# HT-TRS-Interface-Schematic.net
KiCad netlist of a schematic drawn in Altium Designer
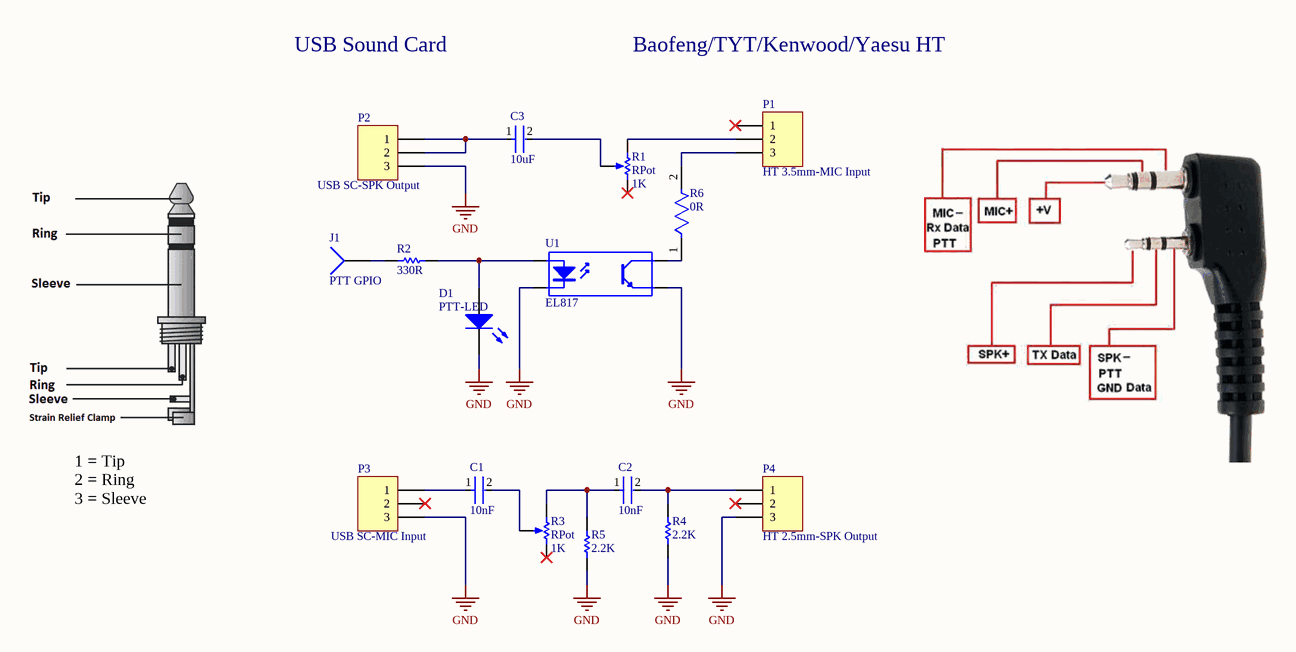
[diagram p0: HT-TRS-Interface-Schematic.SchDoc]

(export (version "E")
  (design (tool "Eeschema 10.0.6"))
  (components
    (comp (ref "C1")
      (value "10nF")
      (footprint "FP-CC0603-DA-MFG")
      (description "CAP CER 10000PF 25V X7R 0603")
      (fields (field (name "TOLERANCE") "0.1") (field (name "MANUFACTURER") "YAGEO"))
      (libsource (lib "Altium Content Vault") (part "11868f565c42a9108669ba33697ecf6"))
    )
    (comp (ref "C2")
      (value "10nF")
      (footprint "FP-CC0603-DA-MFG")
      (description "CAP CER 10000PF 25V X7R 0603")
      (fields (field (name "TOLERANCE") "0.1") (field (name "MANUFACTURER") "YAGEO"))
      (libsource (lib "Altium Content Vault") (part "11868f565c42a9108669ba33697ecf6"))
    )
    (comp (ref "C3")
      (value "10uF")
      (footprint "FP-C1608-MFG")
      (description "CAP CER 10UF 16V X5R 0603")
      (fields
        (field (name "OCTOPART") "https://octopart.com/c1608x5r1c106m080ab-tdk-26013480")
        (field (name "MANUFACTURER") "TDK Corporation")
      )
      (libsource (lib "Altium Content Vault") (part "11868f565c42a9108669ba33697ecf6"))
    )
    (comp (ref "D1")
      (value "PTT-LED")
      (footprint "3.2X1.6X1.1")
      (description "Typical RED, GREEN, YELLOW, AMBER GaAs LED")
      (fields (field (name "PUBLISHER") "Altium Limited"))
      (libsource (lib "Miscellaneous Devices") (part "LED2"))
    )
    (comp (ref "J1")
      (value "PTT GPIO")
      (footprint "PIN1")
      (description "Socket")
      (fields (field (name "PUBLISHER") "Altium Limited"))
      (libsource (lib "Miscellaneous Connectors") (part "Socket"))
    )
    (comp (ref "P1")
      (value "HT 3.5mm-MIC Input")
      (footprint "MHDR1X3")
      (description "Header, 3-Pin")
      (fields (field (name "PUBLISHER") "Altium Limited"))
      (libsource (lib "") (part "MHDR1X3_1"))
    )
    (comp (ref "P2")
      (value "USB SC-SPK Output")
      (footprint "MHDR1X3")
      (description "Header, 3-Pin")
      (fields (field (name "PUBLISHER") "Altium Limited"))
      (libsource (lib "Miscellaneous Connectors") (part "MHDR1X3"))
    )
    (comp (ref "P3")
      (value "USB SC-MIC Input")
      (footprint "MHDR1X3")
      (description "Header, 3-Pin")
      (fields (field (name "PUBLISHER") "Altium Limited"))
      (libsource (lib "Miscellaneous Connectors") (part "MHDR1X3"))
    )
    (comp (ref "P4")
      (value "HT 2.5mm-SPK Output")
      (footprint "MHDR1X3")
      (description "Header, 3-Pin")
      (fields (field (name "PUBLISHER") "Altium Limited"))
      (libsource (lib "") (part "MHDR1X3_1"))
    )
    (comp (ref "R1")
      (value "RPot")
      (footprint "VR5")
      (description "Potentiometer")
      (fields (field (name "ALTIUM_VALUE") "1K") (field (name "PUBLISHER") "Altium Limited"))
      (libsource (lib "Miscellaneous Devices") (part "RPot"))
    )
    (comp (ref "R2")
      (value "330R")
      (footprint "RESC1608X55X30LL15T15")
      (description "Chip Resistor, 330 Ohm, +/- 1%, 0.1 W, -55 to 155 degC, 0603 (1608 Metric), RoHS, Tape and Reel")
      (libsource (lib "Altium Content Vault") (part "RES-2"))
    )
    (comp (ref "R3")
      (value "RPot")
      (footprint "VR5")
      (description "Potentiometer")
      (fields (field (name "ALTIUM_VALUE") "1K") (field (name "PUBLISHER") "Altium Limited"))
      (libsource (lib "Miscellaneous Devices") (part "RPot"))
    )
    (comp (ref "R4")
      (value "2.2K")
      (footprint "RESC1608X55X30ML20T20")
      (fields (field (name "MANUFACTURER") "Panasonic") (field (name "PART NUMBER") "ERA3AEB222V"))
      (libsource (lib "Altium Content Vault") (part "RES"))
    )
    (comp (ref "R5")
      (value "2.2K")
      (footprint "RESC1608X55X30ML20T20")
      (fields (field (name "MANUFACTURER") "Panasonic") (field (name "PART NUMBER") "ERA3AEB222V"))
      (libsource (lib "Altium Content Vault") (part "RES"))
    )
    (comp (ref "R6")
      (value "0R")
      (footprint "FP-ERJ-3GEY0R00V-MFG")
      (description "RES SMD 0 OHM JUMPER 1/10W 0603")
      (fields (field (name "TOLERANCE") "5%") (field (name "MANUFACTURER PART NUMBER") "ERJ-3GEY0R00V"))
      (libsource (lib "Altium Content Vault") (part "1029c3af85768c4190bb7ad29bc67b5"))
    )
    (comp (ref "U1")
      (value "EL817")
      (footprint "DIP-4")
      (description "4-Pin Phototransistor Optocoupler")
      (fields (field (name "PUBLISHER") "Altium Limited"))
      (libsource (lib "Miscellaneous Devices") (part "Optoisolator1"))
    )
  )
  (nets
    (net (code "1") (name "GND") (class "Default")
      (node (ref "D1") (pin "2") (pinfunction "K_2") (pintype "passive"))
      (node (ref "P2") (pin "3") (pinfunction "3_3") (pintype "passive"))
      (node (ref "P3") (pin "3") (pinfunction "3_3") (pintype "passive"))
      (node (ref "P4") (pin "3") (pinfunction "3_3") (pintype "passive"))
      (node (ref "R4") (pin "1") (pinfunction "1_1") (pintype "passive"))
      (node (ref "R5") (pin "1") (pinfunction "1_1") (pintype "passive"))
      (node (ref "U1") (pin "2") (pinfunction "K_2") (pintype "passive"))
      (node (ref "U1") (pin "3") (pinfunction "E_3") (pintype "passive"))
    )
    (net (code "2") (name "Net-(C1-Pad1)") (class "Default")
      (node (ref "C1") (pin "1") (pinfunction "1_1") (pintype "passive"))
      (node (ref "P3") (pin "1") (pinfunction "1_1") (pintype "passive"))
    )
    (net (code "3") (name "Net-(C2-Pad2)") (class "Default")
      (node (ref "C2") (pin "2") (pinfunction "2_2") (pintype "passive"))
      (node (ref "P4") (pin "1") (pinfunction "1_1") (pintype "passive"))
      (node (ref "R4") (pin "2") (pinfunction "2_2") (pintype "passive"))
    )
    (net (code "4") (name "Net-(C3-Pad1)") (class "Default")
      (node (ref "C3") (pin "1") (pinfunction "1_1") (pintype "passive"))
      (node (ref "P2") (pin "1") (pinfunction "1_1") (pintype "passive"))
      (node (ref "P2") (pin "2") (pinfunction "2_2") (pintype "passive"))
    )
    (net (code "5") (name "Net-(D1-A)") (class "Default")
      (node (ref "D1") (pin "1") (pinfunction "A_1") (pintype "passive"))
      (node (ref "R2") (pin "2") (pinfunction "2_2") (pintype "passive"))
      (node (ref "U1") (pin "1") (pinfunction "A_1") (pintype "passive"))
    )
    (net (code "6") (name "Net-(J1-Pad1)") (class "Default")
      (node (ref "J1") (pin "1") (pinfunction "1_1") (pintype "passive"))
      (node (ref "R2") (pin "1") (pinfunction "1_1") (pintype "passive"))
    )
    (net (code "7") (name "Net-(P1-Pad3)") (class "Default")
      (node (ref "P1") (pin "3") (pinfunction "3_3") (pintype "passive"))
      (node (ref "R6") (pin "2") (pinfunction "2_2") (pintype "passive"))
    )
    (net (code "8") (name "Net-(R1-TAP)") (class "Default")
      (node (ref "C3") (pin "2") (pinfunction "2_2") (pintype "passive"))
      (node (ref "R1") (pin "3") (pinfunction "TAP_3") (pintype "passive"))
    )
    (net (code "9") (name "Net-(R1-TOP)") (class "Default")
      (node (ref "P1") (pin "2") (pinfunction "2_2") (pintype "passive"))
      (node (ref "R1") (pin "1") (pinfunction "TOP_1") (pintype "passive"))
    )
    (net (code "10") (name "Net-(R3-TAP)") (class "Default")
      (node (ref "C1") (pin "2") (pinfunction "2_2") (pintype "passive"))
      (node (ref "R3") (pin "3") (pinfunction "TAP_3") (pintype "passive"))
    )
    (net (code "11") (name "Net-(R3-TOP)") (class "Default")
      (node (ref "C2") (pin "1") (pinfunction "1_1") (pintype "passive"))
      (node (ref "R3") (pin "1") (pinfunction "TOP_1") (pintype "passive"))
      (node (ref "R5") (pin "2") (pinfunction "2_2") (pintype "passive"))
    )
    (net (code "12") (name "Net-(U1-C)") (class "Default")
      (node (ref "R6") (pin "1") (pinfunction "1_1") (pintype "passive"))
      (node (ref "U1") (pin "4") (pinfunction "C_4") (pintype "passive"))
    )
    (net (code "13") (name "unconnected-(P1-Pad1)") (class "Default")
      (node (ref "P1") (pin "1") (pinfunction "1_1") (pintype "passive+no_connect"))
    )
    (net (code "14") (name "unconnected-(P3-Pad2)") (class "Default")
      (node (ref "P3") (pin "2") (pinfunction "2_2") (pintype "passive+no_connect"))
    )
    (net (code "15") (name "unconnected-(P4-Pad2)") (class "Default")
      (node (ref "P4") (pin "2") (pinfunction "2_2") (pintype "passive+no_connect"))
    )
    (net (code "16") (name "unconnected-(R1-BOT-Pad2)") (class "Default")
      (node (ref "R1") (pin "2") (pinfunction "BOT_2") (pintype "passive+no_connect"))
    )
    (net (code "17") (name "unconnected-(R3-BOT-Pad2)") (class "Default")
      (node (ref "R3") (pin "2") (pinfunction "BOT_2") (pintype "passive+no_connect"))
    )
  )
)
